# ControlBox.net
KiCad netlist of a schematic drawn in Altium Designer
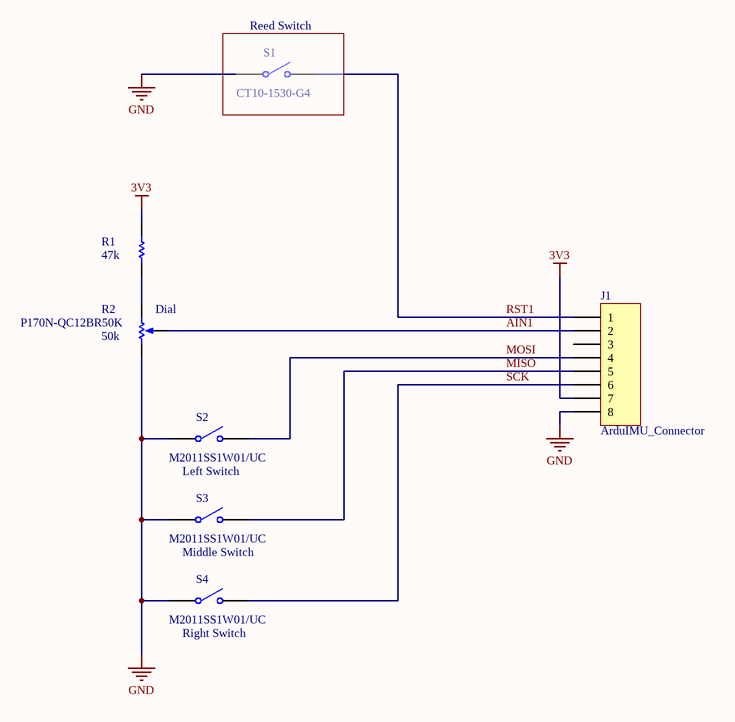
[diagram p0: ControlBox.SchDoc]

(export (version "E")
  (design (tool "Eeschema 10.0.6"))
  (components
    (comp (ref "J1")
      (value "ArduIMU_Connector")
      (footprint "HDR1X8")
      (description "Header, 8-Pin")
      (fields (field (name "PUBLISHER") "Altium Limited"))
      (libsource (lib "Miscellaneous Connectors") (part "Header 8"))
    )
    (comp (ref "R1")
      (value "47k")
      (footprint "AXIAL-0.3")
      (description "Resistor")
      (fields (field (name "PUBLISHER") "Altium Limited"))
      (libsource (lib "Miscellaneous Devices") (part "Res1"))
    )
    (comp (ref "R2")
      (value "P170N-QC12BR50K")
      (footprint "VR5")
      (description "Potentiometer")
      (fields (field (name "ALTIUM_VALUE") "50k") (field (name "PUBLISHER") "Altium Limited"))
      (libsource (lib "Miscellaneous Devices") (part "RPot"))
    )
    (comp (ref "S1")
      (value "CT10-1530-G4")
      (footprint "SPST-2")
      (description "Single-Pole, Single-Throw Switch")
      (fields (field (name "PUBLISHER") "Altium Limited"))
      (libsource (lib "Miscellaneous Devices") (part "SW-SPST"))
    )
    (comp (ref "S2")
      (value "M2011SS1W01/UC")
      (footprint "SPST-2")
      (description "Single-Pole, Single-Throw Switch")
      (fields (field (name "PUBLISHER") "Altium Limited"))
      (libsource (lib "Miscellaneous Devices") (part "SW-SPST"))
    )
    (comp (ref "S3")
      (value "M2011SS1W01/UC")
      (footprint "SPST-2")
      (description "Single-Pole, Single-Throw Switch")
      (fields (field (name "PUBLISHER") "Altium Limited"))
      (libsource (lib "Miscellaneous Devices") (part "SW-SPST"))
    )
    (comp (ref "S4")
      (value "M2011SS1W01/UC")
      (footprint "SPST-2")
      (description "Single-Pole, Single-Throw Switch")
      (fields (field (name "PUBLISHER") "Altium Limited"))
      (libsource (lib "Miscellaneous Devices") (part "SW-SPST"))
    )
  )
  (nets
    (net (code "1") (name "/AIN1") (class "Default")
      (node (ref "J1") (pin "2") (pinfunction "2_2") (pintype "passive"))
      (node (ref "R2") (pin "3") (pinfunction "TAP_3") (pintype "passive"))
    )
    (net (code "2") (name "/MISO") (class "Default")
      (node (ref "J1") (pin "5") (pinfunction "5_5") (pintype "passive"))
      (node (ref "S3") (pin "2") (pinfunction "NO_2") (pintype "passive"))
    )
    (net (code "3") (name "/MOSI") (class "Default")
      (node (ref "J1") (pin "4") (pinfunction "4_4") (pintype "passive"))
      (node (ref "S2") (pin "2") (pinfunction "NO_2") (pintype "passive"))
    )
    (net (code "4") (name "/RST1") (class "Default")
      (node (ref "J1") (pin "1") (pinfunction "1_1") (pintype "passive"))
      (node (ref "S1") (pin "2") (pinfunction "NO_2") (pintype "passive"))
    )
    (net (code "5") (name "/SCK") (class "Default")
      (node (ref "J1") (pin "6") (pinfunction "6_6") (pintype "passive"))
      (node (ref "S4") (pin "2") (pinfunction "NO_2") (pintype "passive"))
    )
    (net (code "6") (name "3V3") (class "Default")
      (node (ref "J1") (pin "7") (pinfunction "7_7") (pintype "passive"))
      (node (ref "R1") (pin "2") (pinfunction "2_2") (pintype "passive"))
    )
    (net (code "7") (name "GND") (class "Default")
      (node (ref "J1") (pin "8") (pinfunction "8_8") (pintype "passive"))
      (node (ref "R2") (pin "1") (pinfunction "TOP_1") (pintype "passive"))
      (node (ref "S1") (pin "1") (pinfunction "COMMON_1") (pintype "passive"))
      (node (ref "S2") (pin "1") (pinfunction "COMMON_1") (pintype "passive"))
      (node (ref "S3") (pin "1") (pinfunction "COMMON_1") (pintype "passive"))
      (node (ref "S4") (pin "1") (pinfunction "COMMON_1") (pintype "passive"))
    )
    (net (code "8") (name "Net-(R2-BOT)") (class "Default")
      (node (ref "R1") (pin "1") (pinfunction "1_1") (pintype "passive"))
      (node (ref "R2") (pin "2") (pinfunction "BOT_2") (pintype "passive"))
    )
    (net (code "9") (name "unconnected-(J1-Pad3)") (class "Default")
      (node (ref "J1") (pin "3") (pinfunction "3_3") (pintype "passive"))
    )
  )
)
